# schema_sensors.net
KiCad netlist of a schematic drawn in EAGLE
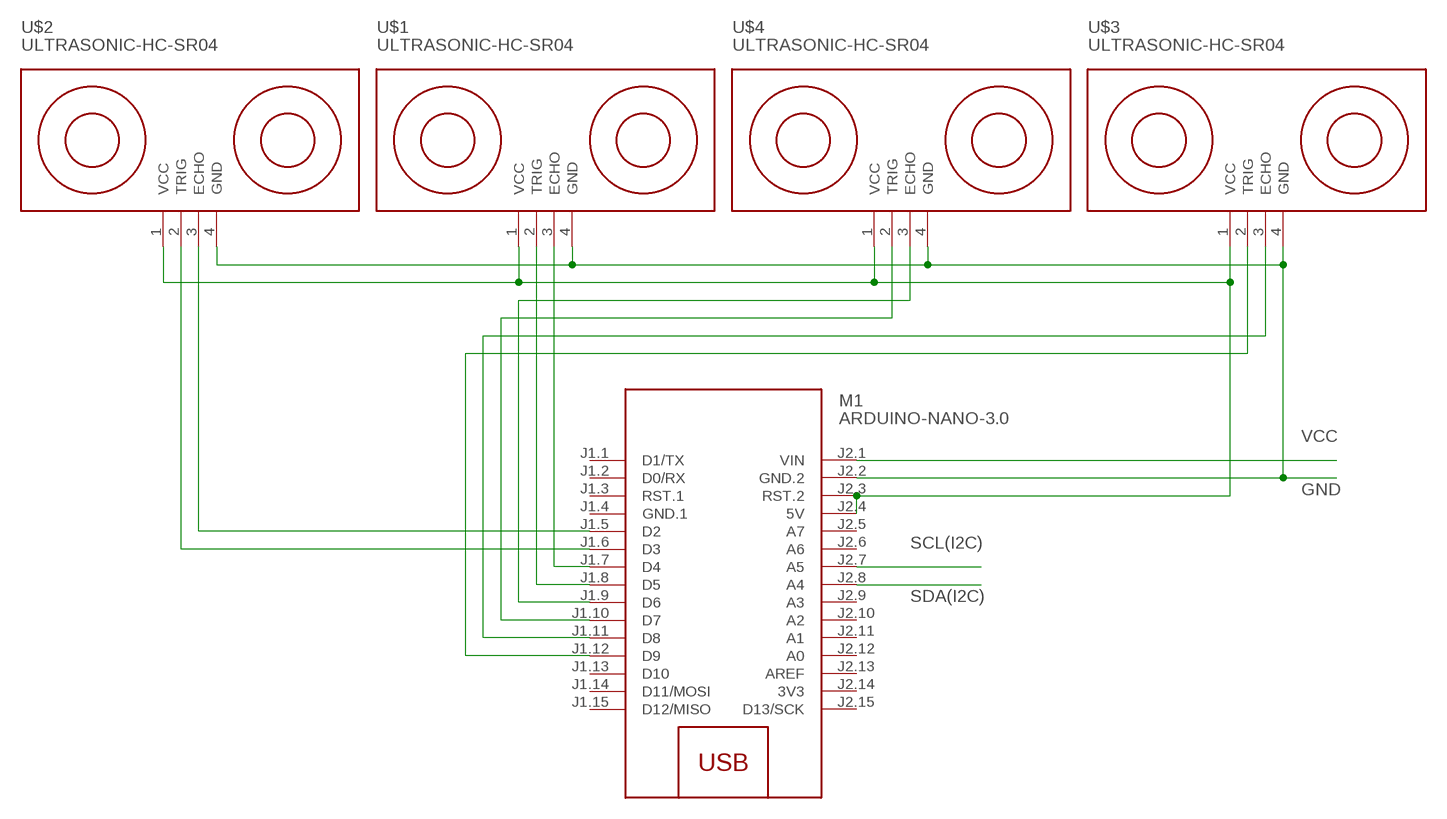
[diagram p0: schematic, sheet 1]

(export (version "E")
  (design (tool "Eeschema 10.0.6"))
  (components
    (comp (ref "M1")
      (value "ARDUINO-NANO-3.0")
      (footprint "eagle-import:ARDUINO-NANO-3.0")
      (libsource (lib "eagle-import") (part "ARDUINO-NANO-3.0"))
    )
    (comp (ref "U$1")
      (value "ULTRASONIC-HC-SR04")
      (footprint "eagle-import:ULTRASONIC-HC-SR04")
      (libsource (lib "eagle-import") (part "ULTRASONIC-HC-SR04"))
    )
    (comp (ref "U$2")
      (value "ULTRASONIC-HC-SR04")
      (footprint "eagle-import:ULTRASONIC-HC-SR04")
      (libsource (lib "eagle-import") (part "ULTRASONIC-HC-SR04"))
    )
    (comp (ref "U$3")
      (value "ULTRASONIC-HC-SR04")
      (footprint "eagle-import:ULTRASONIC-HC-SR04")
      (libsource (lib "eagle-import") (part "ULTRASONIC-HC-SR04"))
    )
    (comp (ref "U$4")
      (value "ULTRASONIC-HC-SR04")
      (footprint "eagle-import:ULTRASONIC-HC-SR04")
      (libsource (lib "eagle-import") (part "ULTRASONIC-HC-SR04"))
    )
  )
  (nets
    (net (code "1") (name "/3V3") (class "Default")
      (node (ref "M1") (pin "J2.14") (pinfunction "3V3_J2.14") (pintype "power_in"))
    )
    (net (code "2") (name "/GND") (class "Default")
      (node (ref "M1") (pin "J2.2") (pinfunction "GND.2_J2.2") (pintype "power_in"))
      (node (ref "U$1") (pin "4") (pinfunction "GND_4") (pintype "power_in"))
      (node (ref "U$2") (pin "4") (pinfunction "GND_4") (pintype "power_in"))
      (node (ref "U$3") (pin "4") (pinfunction "GND_4") (pintype "power_in"))
      (node (ref "U$4") (pin "4") (pinfunction "GND_4") (pintype "power_in"))
    )
    (net (code "3") (name "/GND.1") (class "Default")
      (node (ref "M1") (pin "J1.4") (pinfunction "GND.1_J1.4") (pintype "power_in"))
    )
    (net (code "4") (name "/SCL(I2C)") (class "Default")
      (node (ref "M1") (pin "J2.7") (pinfunction "A5_J2.7") (pintype "bidirectional"))
    )
    (net (code "5") (name "/SDA(I2C)") (class "Default")
      (node (ref "M1") (pin "J2.8") (pinfunction "A4_J2.8") (pintype "bidirectional"))
    )
    (net (code "6") (name "/VCC") (class "Default")
      (node (ref "M1") (pin "J2.1") (pinfunction "VIN_J2.1") (pintype "power_in"))
    )
    (net (code "7") (name "Net-(M1-5V)") (class "Default")
      (node (ref "M1") (pin "J2.3") (pinfunction "RST.2_J2.3") (pintype "bidirectional"))
      (node (ref "M1") (pin "J2.4") (pinfunction "5V_J2.4") (pintype "power_in"))
      (node (ref "U$1") (pin "1") (pinfunction "VCC_1") (pintype "power_in"))
      (node (ref "U$2") (pin "1") (pinfunction "VCC_1") (pintype "power_in"))
      (node (ref "U$3") (pin "1") (pinfunction "VCC_1") (pintype "power_in"))
      (node (ref "U$4") (pin "1") (pinfunction "VCC_1") (pintype "power_in"))
    )
    (net (code "8") (name "Net-(M1-D2)") (class "Default")
      (node (ref "M1") (pin "J1.5") (pinfunction "D2_J1.5") (pintype "bidirectional"))
      (node (ref "U$2") (pin "3") (pinfunction "ECHO_3") (pintype "output"))
    )
    (net (code "9") (name "Net-(M1-D3)") (class "Default")
      (node (ref "M1") (pin "J1.6") (pinfunction "D3_J1.6") (pintype "bidirectional"))
      (node (ref "U$2") (pin "2") (pinfunction "TRIG_2") (pintype "input"))
    )
    (net (code "10") (name "Net-(M1-D4)") (class "Default")
      (node (ref "M1") (pin "J1.7") (pinfunction "D4_J1.7") (pintype "bidirectional"))
      (node (ref "U$1") (pin "3") (pinfunction "ECHO_3") (pintype "output"))
    )
    (net (code "11") (name "Net-(M1-D5)") (class "Default")
      (node (ref "M1") (pin "J1.8") (pinfunction "D5_J1.8") (pintype "bidirectional"))
      (node (ref "U$1") (pin "2") (pinfunction "TRIG_2") (pintype "input"))
    )
    (net (code "12") (name "Net-(M1-D6)") (class "Default")
      (node (ref "M1") (pin "J1.9") (pinfunction "D6_J1.9") (pintype "bidirectional"))
      (node (ref "U$4") (pin "3") (pinfunction "ECHO_3") (pintype "output"))
    )
    (net (code "13") (name "Net-(M1-D7)") (class "Default")
      (node (ref "M1") (pin "J1.10") (pinfunction "D7_J1.10") (pintype "bidirectional"))
      (node (ref "U$4") (pin "2") (pinfunction "TRIG_2") (pintype "input"))
    )
    (net (code "14") (name "Net-(M1-D8)") (class "Default")
      (node (ref "M1") (pin "J1.11") (pinfunction "D8_J1.11") (pintype "bidirectional"))
      (node (ref "U$3") (pin "3") (pinfunction "ECHO_3") (pintype "output"))
    )
    (net (code "15") (name "Net-(M1-D9)") (class "Default")
      (node (ref "M1") (pin "J1.12") (pinfunction "D9_J1.12") (pintype "bidirectional"))
      (node (ref "U$3") (pin "2") (pinfunction "TRIG_2") (pintype "input"))
    )
    (net (code "16") (name "unconnected-(M1-A0-PadJ2.12)") (class "Default")
      (node (ref "M1") (pin "J2.12") (pinfunction "A0_J2.12") (pintype "bidirectional"))
    )
    (net (code "17") (name "unconnected-(M1-A1-PadJ2.11)") (class "Default")
      (node (ref "M1") (pin "J2.11") (pinfunction "A1_J2.11") (pintype "bidirectional"))
    )
    (net (code "18") (name "unconnected-(M1-A2-PadJ2.10)") (class "Default")
      (node (ref "M1") (pin "J2.10") (pinfunction "A2_J2.10") (pintype "bidirectional"))
    )
    (net (code "19") (name "unconnected-(M1-A3-PadJ2.9)") (class "Default")
      (node (ref "M1") (pin "J2.9") (pinfunction "A3_J2.9") (pintype "bidirectional"))
    )
    (net (code "20") (name "unconnected-(M1-A6-PadJ2.6)") (class "Default")
      (node (ref "M1") (pin "J2.6") (pinfunction "A6_J2.6") (pintype "bidirectional"))
    )
    (net (code "21") (name "unconnected-(M1-A7-PadJ2.5)") (class "Default")
      (node (ref "M1") (pin "J2.5") (pinfunction "A7_J2.5") (pintype "bidirectional"))
    )
    (net (code "22") (name "unconnected-(M1-AREF-PadJ2.13)") (class "Default")
      (node (ref "M1") (pin "J2.13") (pinfunction "AREF_J2.13") (pintype "bidirectional"))
    )
    (net (code "23") (name "unconnected-(M1-D0{slash}RX-PadJ1.2)") (class "Default")
      (node (ref "M1") (pin "J1.2") (pinfunction "D0/RX_J1.2") (pintype "bidirectional"))
    )
    (net (code "24") (name "unconnected-(M1-D1{slash}TX-PadJ1.1)") (class "Default")
      (node (ref "M1") (pin "J1.1") (pinfunction "D1/TX_J1.1") (pintype "bidirectional"))
    )
    (net (code "25") (name "unconnected-(M1-D10-PadJ1.13)") (class "Default")
      (node (ref "M1") (pin "J1.13") (pinfunction "D10_J1.13") (pintype "bidirectional"))
    )
    (net (code "26") (name "unconnected-(M1-D11{slash}MOSI-PadJ1.14)") (class "Default")
      (node (ref "M1") (pin "J1.14") (pinfunction "D11/MOSI_J1.14") (pintype "bidirectional"))
    )
    (net (code "27") (name "unconnected-(M1-D12{slash}MISO-PadJ1.15)") (class "Default")
      (node (ref "M1") (pin "J1.15") (pinfunction "D12/MISO_J1.15") (pintype "bidirectional"))
    )
    (net (code "28") (name "unconnected-(M1-D13{slash}SCK-PadJ2.15)") (class "Default")
      (node (ref "M1") (pin "J2.15") (pinfunction "D13/SCK_J2.15") (pintype "bidirectional"))
    )
    (net (code "29") (name "unconnected-(M1-RST.1-PadJ1.3)") (class "Default")
      (node (ref "M1") (pin "J1.3") (pinfunction "RST.1_J1.3") (pintype "bidirectional"))
    )
  )
)
